# BattPower.net
KiCad netlist of a schematic drawn in Altium Designer
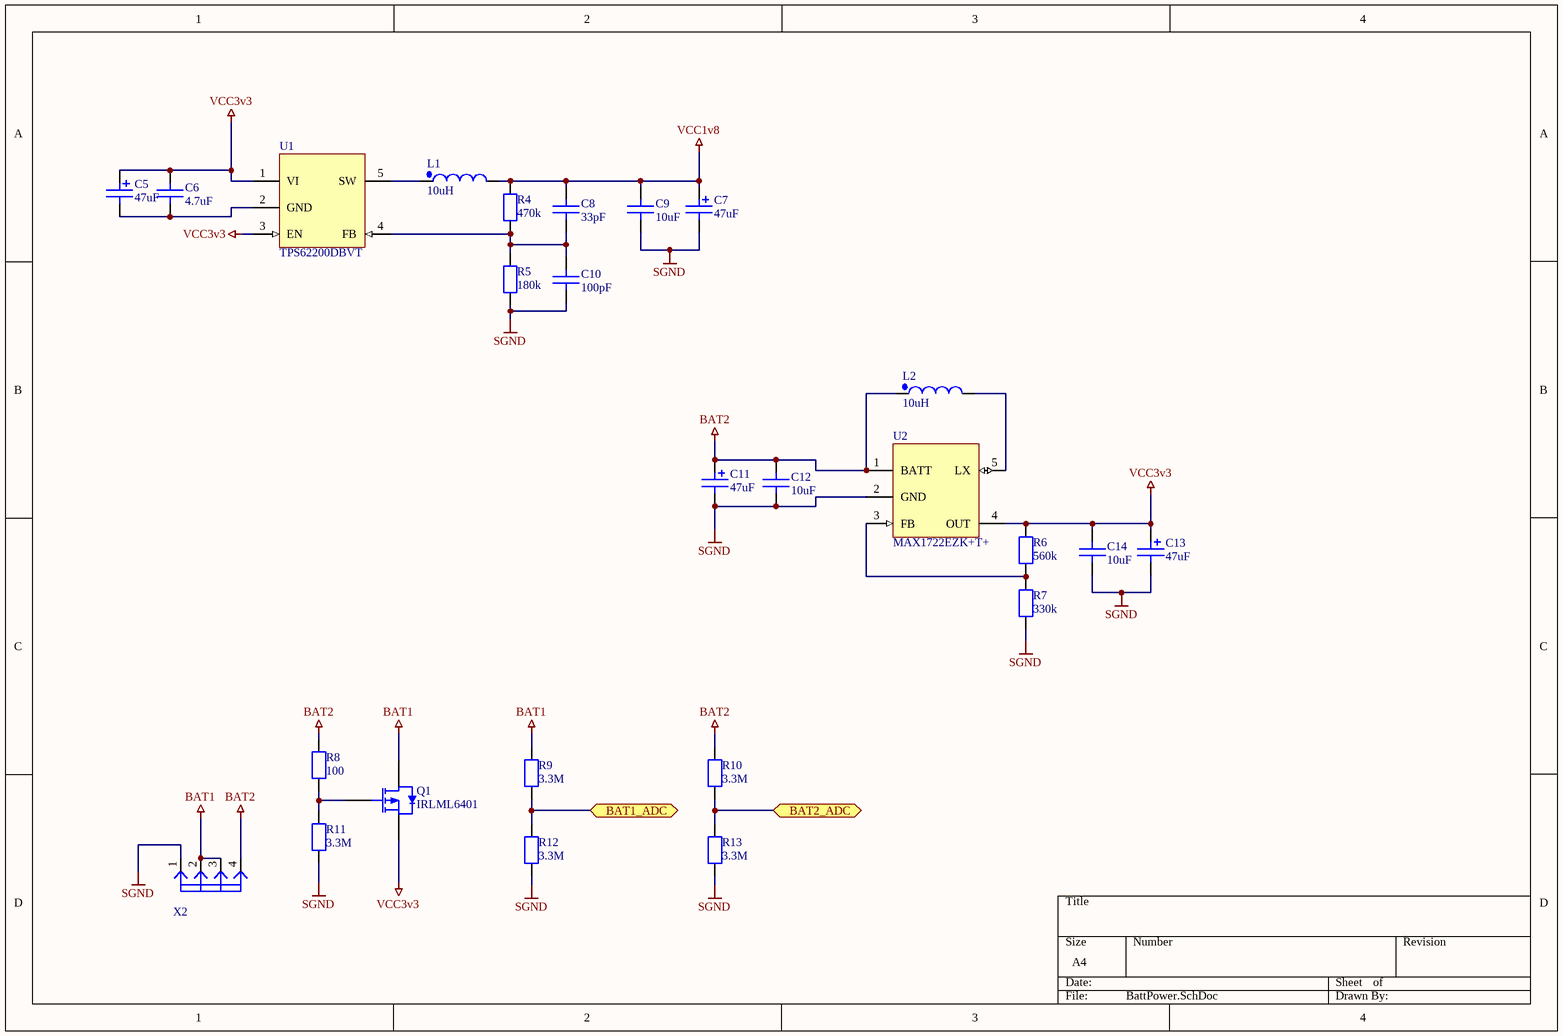
[diagram p0: BattPower.SchDoc]

(export (version "E")
  (design (tool "Eeschema 10.0.6"))
  (components
    (comp (ref "C5")
      (value "47uF")
      (footprint "TC2917")
      (description "C47uF-10V-tant")
      (fields (field (name "VOLTAGE") "10V"))
      (libsource (lib "MCounter_Common") (part "C47uF-10V-tant"))
    )
    (comp (ref "C6")
      (value "4.7uF")
      (footprint "C0805")
      (description "C4.7uF-16V")
      (fields (field (name "VOLTAGE") "16V"))
      (libsource (lib "MCounter_Common") (part "C4.7uF-16V"))
    )
    (comp (ref "C7")
      (value "47uF")
      (footprint "TC2917")
      (description "C47uF-10V-tant")
      (fields (field (name "VOLTAGE") "10V"))
      (libsource (lib "MCounter_Common") (part "C47uF-10V-tant"))
    )
    (comp (ref "C8")
      (value "33pF")
      (footprint "C0805")
      (description "C33pF-50V")
      (fields (field (name "VOLTAGE") "50V"))
      (libsource (lib "MCounter_Common") (part "C33pF-50V"))
    )
    (comp (ref "C9")
      (value "10uF")
      (footprint "C0805")
      (description "C10uF-16V")
      (fields (field (name "VOLTAGE") "16V"))
      (libsource (lib "MCounter_Common") (part "C10uF-16V"))
    )
    (comp (ref "C10")
      (value "100pF")
      (footprint "C0805")
      (description "C100pF-50V")
      (fields (field (name "VOLTAGE") "50V"))
      (libsource (lib "MCounter_Common") (part "C100pF-50V"))
    )
    (comp (ref "C11")
      (value "47uF")
      (footprint "TC2917")
      (description "C47uF-10V-tant")
      (fields (field (name "VOLTAGE") "10V"))
      (libsource (lib "MCounter_Common") (part "C47uF-10V-tant"))
    )
    (comp (ref "C12")
      (value "10uF")
      (footprint "C0805")
      (description "C10uF-16V")
      (fields (field (name "VOLTAGE") "16V"))
      (libsource (lib "MCounter_Common") (part "C10uF-16V"))
    )
    (comp (ref "C13")
      (value "47uF")
      (footprint "TC2917")
      (description "C47uF-10V-tant")
      (fields (field (name "VOLTAGE") "10V"))
      (libsource (lib "MCounter_Common") (part "C47uF-10V-tant"))
    )
    (comp (ref "C14")
      (value "10uF")
      (footprint "C0805")
      (description "C10uF-16V")
      (fields (field (name "VOLTAGE") "16V"))
      (libsource (lib "MCounter_Common") (part "C10uF-16V"))
    )
    (comp (ref "L1")
      (value "10uH")
      (footprint "CD54-CDRH4D")
      (description "Inductor with Winding Polarity Marking")
      (fields (field (name "Comment") "CD54"))
      (libsource (lib "MCounter_Common") (part "CD54NP-100M"))
    )
    (comp (ref "L2")
      (value "10uH")
      (footprint "CD54-CDRH4D")
      (description "Inductor with Winding Polarity Marking")
      (fields (field (name "Comment") "CD54"))
      (libsource (lib "MCounter_Common") (part "CD54NP-100M"))
    )
    (comp (ref "Q1")
      (value "IRLML6401")
      (footprint "SOT23_N")
      (description "P-Channel Power MOSFET")
      (libsource (lib "MCounter_Common") (part "IRLML6401"))
    )
    (comp (ref "R4")
      (value "470k")
      (footprint "R0805")
      (description "R470k-1%")
      (libsource (lib "MCounter_Common") (part "R470k-1%"))
    )
    (comp (ref "R5")
      (value "180k")
      (footprint "R0805")
      (description "R180k-1%")
      (libsource (lib "MCounter_Common") (part "R180k-1%"))
    )
    (comp (ref "R6")
      (value "560k")
      (footprint "R0805")
      (description "R560k-1%")
      (libsource (lib "MCounter_Common") (part "R560k-1%"))
    )
    (comp (ref "R7")
      (value "330k")
      (footprint "R0805")
      (description "R330k-1%")
      (libsource (lib "MCounter_Common") (part "R330k-1%"))
    )
    (comp (ref "R8")
      (value "100")
      (footprint "R0805")
      (description "R-100-5%")
      (fields (field (name "Comment") "R100-5%"))
      (libsource (lib "MCounter_Common") (part "R100-5%"))
    )
    (comp (ref "R9")
      (value "3.3M")
      (footprint "R0805")
      (description "R3.3M-5%")
      (libsource (lib "MCounter_Common") (part "R3.3M-5%"))
    )
    (comp (ref "R10")
      (value "3.3M")
      (footprint "R0805")
      (description "R3.3M-5%")
      (libsource (lib "MCounter_Common") (part "R3.3M-5%"))
    )
    (comp (ref "R11")
      (value "3.3M")
      (footprint "R0805")
      (description "R3.3M-5%")
      (libsource (lib "MCounter_Common") (part "R3.3M-5%"))
    )
    (comp (ref "R12")
      (value "3.3M")
      (footprint "R0805")
      (description "R3.3M-5%")
      (libsource (lib "MCounter_Common") (part "R3.3M-5%"))
    )
    (comp (ref "R13")
      (value "3.3M")
      (footprint "R0805")
      (description "R3.3M-5%")
      (libsource (lib "MCounter_Common") (part "R3.3M-5%"))
    )
    (comp (ref "U1")
      (value "TPS62200DBVT")
      (footprint "5ST1_N")
      (description "High efficiency step-down DC-DC convertor, 5-pin SOT23")
      (libsource (lib "MCounter_Common") (part "TPS62200DBVT"))
    )
    (comp (ref "U2")
      (value "MAX1722EZK+T+")
      (footprint "5ST1_N")
      (description "High efficiency step-down DC-DC convertor, 5-pin SOT23")
      (libsource (lib "MCounter_Common") (part "MAX1722EZK+T+"))
    )
    (comp (ref "X2") (value "PLS-4") (footprint "PLS-4") (libsource (lib "MCounter_Common") (part "PLS-4")))
  )
  (nets
    (net (code "1") (name "/BAT1_ADC") (class "Default")
      (node (ref "R12") (pin "2") (pinfunction "2_2") (pintype "passive"))
      (node (ref "R9") (pin "1") (pinfunction "1_1") (pintype "passive"))
    )
    (net (code "2") (name "/BAT2_ADC") (class "Default")
      (node (ref "R10") (pin "1") (pinfunction "1_1") (pintype "passive"))
      (node (ref "R13") (pin "2") (pinfunction "2_2") (pintype "passive"))
    )
    (net (code "3") (name "BAT1") (class "Default")
      (node (ref "Q1") (pin "3") (pinfunction "D_3") (pintype "passive"))
      (node (ref "R9") (pin "2") (pinfunction "2_2") (pintype "passive"))
      (node (ref "X2") (pin "2") (pinfunction "2_2") (pintype "passive"))
      (node (ref "X2") (pin "3") (pinfunction "3_3") (pintype "passive"))
    )
    (net (code "4") (name "BAT2") (class "Default")
      (node (ref "C11") (pin "1") (pinfunction "1_1") (pintype "passive"))
      (node (ref "C12") (pin "2") (pinfunction "2_2") (pintype "passive"))
      (node (ref "L2") (pin "1") (pinfunction "1_1") (pintype "passive"))
      (node (ref "R10") (pin "2") (pinfunction "2_2") (pintype "passive"))
      (node (ref "R8") (pin "2") (pinfunction "2_2") (pintype "passive"))
      (node (ref "U2") (pin "1") (pinfunction "BATT_1") (pintype "power_in"))
      (node (ref "X2") (pin "4") (pinfunction "4_4") (pintype "passive"))
    )
    (net (code "5") (name "Net-(Q1-G)") (class "Default")
      (node (ref "Q1") (pin "1") (pinfunction "G_1") (pintype "passive"))
      (node (ref "R11") (pin "2") (pinfunction "2_2") (pintype "passive"))
      (node (ref "R8") (pin "1") (pinfunction "1_1") (pintype "passive"))
    )
    (net (code "6") (name "Net-(U1-FB)") (class "Default")
      (node (ref "C10") (pin "2") (pinfunction "2_2") (pintype "passive"))
      (node (ref "C8") (pin "1") (pinfunction "1_1") (pintype "passive"))
      (node (ref "R4") (pin "1") (pinfunction "1_1") (pintype "passive"))
      (node (ref "R5") (pin "2") (pinfunction "2_2") (pintype "passive"))
      (node (ref "U1") (pin "4") (pinfunction "FB_4") (pintype "input"))
    )
    (net (code "7") (name "Net-(U1-GND)") (class "Default")
      (node (ref "C5") (pin "2") (pinfunction "2_2") (pintype "passive"))
      (node (ref "C6") (pin "1") (pinfunction "1_1") (pintype "passive"))
      (node (ref "U1") (pin "2") (pinfunction "GND_2") (pintype "power_in"))
    )
    (net (code "8") (name "Net-(U1-SW)") (class "Default")
      (node (ref "L1") (pin "1") (pinfunction "1_1") (pintype "passive"))
      (node (ref "U1") (pin "5") (pinfunction "SW_5") (pintype "power_in"))
    )
    (net (code "9") (name "Net-(U2-FB)") (class "Default")
      (node (ref "R6") (pin "1") (pinfunction "1_1") (pintype "passive"))
      (node (ref "R7") (pin "2") (pinfunction "2_2") (pintype "passive"))
      (node (ref "U2") (pin "3") (pinfunction "FB_3") (pintype "input"))
    )
    (net (code "10") (name "Net-(U2-LX)") (class "Default")
      (node (ref "L2") (pin "2") (pinfunction "2_2") (pintype "passive"))
      (node (ref "U2") (pin "5") (pinfunction "LX_5") (pintype "bidirectional"))
    )
    (net (code "11") (name "SGND") (class "Default")
      (node (ref "C10") (pin "1") (pinfunction "1_1") (pintype "passive"))
      (node (ref "C11") (pin "2") (pinfunction "2_2") (pintype "passive"))
      (node (ref "C12") (pin "1") (pinfunction "1_1") (pintype "passive"))
      (node (ref "C13") (pin "2") (pinfunction "2_2") (pintype "passive"))
      (node (ref "C14") (pin "1") (pinfunction "1_1") (pintype "passive"))
      (node (ref "C7") (pin "2") (pinfunction "2_2") (pintype "passive"))
      (node (ref "C9") (pin "1") (pinfunction "1_1") (pintype "passive"))
      (node (ref "R11") (pin "1") (pinfunction "1_1") (pintype "passive"))
      (node (ref "R12") (pin "1") (pinfunction "1_1") (pintype "passive"))
      (node (ref "R13") (pin "1") (pinfunction "1_1") (pintype "passive"))
      (node (ref "R5") (pin "1") (pinfunction "1_1") (pintype "passive"))
      (node (ref "R7") (pin "1") (pinfunction "1_1") (pintype "passive"))
      (node (ref "U2") (pin "2") (pinfunction "GND_2") (pintype "power_in"))
      (node (ref "X2") (pin "1") (pinfunction "1_1") (pintype "passive"))
    )
    (net (code "12") (name "VCC1v8") (class "Default")
      (node (ref "C7") (pin "1") (pinfunction "1_1") (pintype "passive"))
      (node (ref "C8") (pin "2") (pinfunction "2_2") (pintype "passive"))
      (node (ref "C9") (pin "2") (pinfunction "2_2") (pintype "passive"))
      (node (ref "L1") (pin "2") (pinfunction "2_2") (pintype "passive"))
      (node (ref "R4") (pin "2") (pinfunction "2_2") (pintype "passive"))
    )
    (net (code "13") (name "VCC3v3") (class "Default")
      (node (ref "C13") (pin "1") (pinfunction "1_1") (pintype "passive"))
      (node (ref "C14") (pin "2") (pinfunction "2_2") (pintype "passive"))
      (node (ref "C5") (pin "1") (pinfunction "1_1") (pintype "passive"))
      (node (ref "C6") (pin "2") (pinfunction "2_2") (pintype "passive"))
      (node (ref "Q1") (pin "2") (pinfunction "S_2") (pintype "passive"))
      (node (ref "R6") (pin "2") (pinfunction "2_2") (pintype "passive"))
      (node (ref "U1") (pin "1") (pinfunction "VI_1") (pintype "power_in"))
      (node (ref "U1") (pin "3") (pinfunction "EN_3") (pintype "input"))
      (node (ref "U2") (pin "4") (pinfunction "OUT_4") (pintype "power_in"))
    )
  )
)
